# 05_-_CPU_IO.net
KiCad netlist of a schematic drawn in Altium Designer
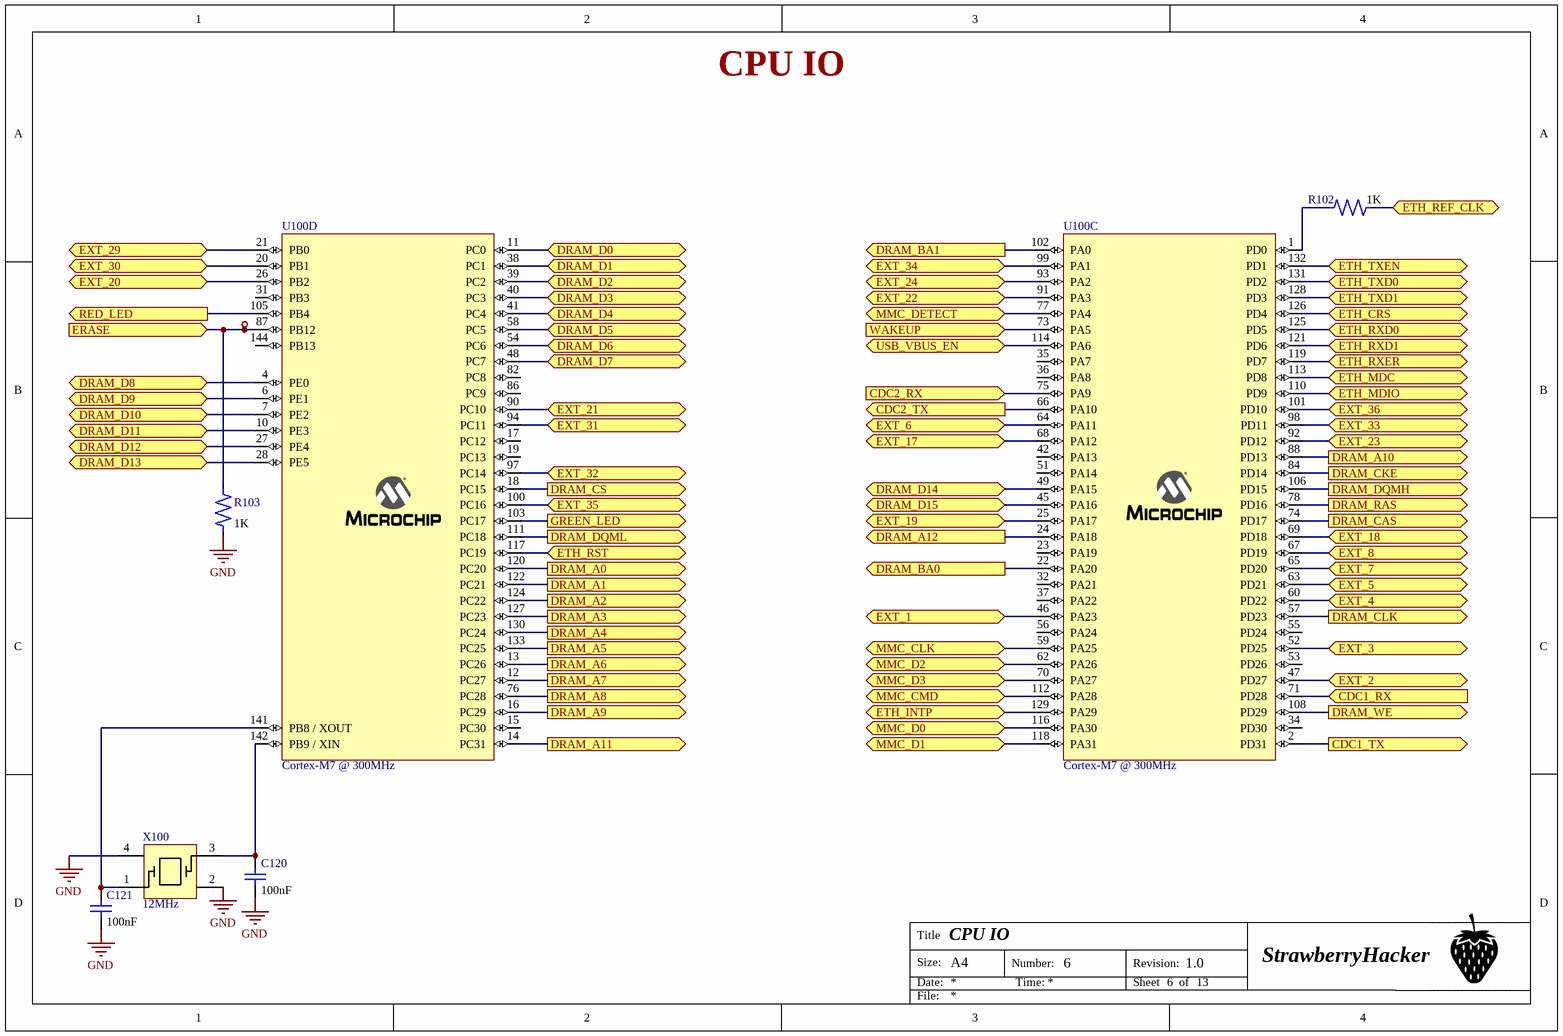
[diagram p0: [05] - CPU IO.SchDoc]

(export (version "E")
  (design (tool "Eeschema 10.0.6"))
  (components
    (comp (ref "C120")
      (value "100nF")
      (footprint "C0402")
      (description "C0402")
      (fields (field (name "Comment") "04023C103KAT2A"))
      (libsource (lib "Passive components") (part "04023C103KAT2A"))
    )
    (comp (ref "C121")
      (value "100nF")
      (footprint "C0402")
      (description "C0402")
      (fields (field (name "Comment") "04023C103KAT2A"))
      (libsource (lib "Passive components") (part "04023C103KAT2A"))
    )
    (comp (ref "R102")
      (value "1K")
      (footprint "R0402")
      (description "R0402")
      (fields (field (name "Comment") "CRCW04020000Z0ED"))
      (libsource (lib "Passive components") (part "CRCW04020000Z0ED"))
    )
    (comp (ref "R103")
      (value "1K")
      (footprint "R0402")
      (description "R0402")
      (fields (field (name "Comment") "CRCW04020000Z0ED"))
      (libsource (lib "Passive components") (part "CRCW04020000Z0ED"))
    )
    (comp (ref "TP100")
      (value "Test point")
      (footprint "TEST POINT")
      (libsource (lib "Miscellaneous") (part "Test point"))
    )
    (comp (ref "U100")
      (value "Cortex-M7 @ 300MHz")
      (footprint "ATSAMS70Q21A-AN")
      (description "ATSAMS70Q21")
      (libsource (lib "Microcontrollers") (part "ATSAMS70Q21A-AN"))
    )
    (comp (ref "X100")
      (value "12MHz")
      (footprint "MCSJK-7U-12.00-12-30-80-B-30")
      (description "Crystal 12MHz 3.2mm x 2.5mm")
      (libsource (lib "Crystals") (part "MCSJK-7U-12.00-12-30-80-B-30"))
    )
  )
  (nets
    (net (code "1") (name "/CDC1_RX") (class "Default")
      (node (ref "U100") (pin "71") (pinfunction "PD28_71") (pintype "bidirectional"))
    )
    (net (code "2") (name "/CDC1_TX") (class "Default")
      (node (ref "U100") (pin "2") (pinfunction "PD31_2") (pintype "bidirectional"))
    )
    (net (code "3") (name "/CDC2_RX") (class "Default")
      (node (ref "U100") (pin "75") (pinfunction "PA9_75") (pintype "bidirectional"))
    )
    (net (code "4") (name "/CDC2_TX") (class "Default")
      (node (ref "U100") (pin "66") (pinfunction "PA10_66") (pintype "bidirectional"))
    )
    (net (code "5") (name "/DRAM_A0") (class "Default")
      (node (ref "U100") (pin "120") (pinfunction "PC20_120") (pintype "bidirectional"))
    )
    (net (code "6") (name "/DRAM_A1") (class "Default")
      (node (ref "U100") (pin "122") (pinfunction "PC21_122") (pintype "bidirectional"))
    )
    (net (code "7") (name "/DRAM_A2") (class "Default")
      (node (ref "U100") (pin "124") (pinfunction "PC22_124") (pintype "bidirectional"))
    )
    (net (code "8") (name "/DRAM_A3") (class "Default")
      (node (ref "U100") (pin "127") (pinfunction "PC23_127") (pintype "bidirectional"))
    )
    (net (code "9") (name "/DRAM_A4") (class "Default")
      (node (ref "U100") (pin "130") (pinfunction "PC24_130") (pintype "bidirectional"))
    )
    (net (code "10") (name "/DRAM_A5") (class "Default")
      (node (ref "U100") (pin "133") (pinfunction "PC25_133") (pintype "bidirectional"))
    )
    (net (code "11") (name "/DRAM_A6") (class "Default")
      (node (ref "U100") (pin "13") (pinfunction "PC26_13") (pintype "bidirectional"))
    )
    (net (code "12") (name "/DRAM_A7") (class "Default")
      (node (ref "U100") (pin "12") (pinfunction "PC27_12") (pintype "bidirectional"))
    )
    (net (code "13") (name "/DRAM_A8") (class "Default")
      (node (ref "U100") (pin "76") (pinfunction "PC28_76") (pintype "bidirectional"))
    )
    (net (code "14") (name "/DRAM_A9") (class "Default")
      (node (ref "U100") (pin "16") (pinfunction "PC29_16") (pintype "bidirectional"))
    )
    (net (code "15") (name "/DRAM_A10") (class "Default")
      (node (ref "U100") (pin "88") (pinfunction "PD13_88") (pintype "bidirectional"))
    )
    (net (code "16") (name "/DRAM_A11") (class "Default")
      (node (ref "U100") (pin "14") (pinfunction "PC31_14") (pintype "bidirectional"))
    )
    (net (code "17") (name "/DRAM_A12") (class "Default")
      (node (ref "U100") (pin "24") (pinfunction "PA18_24") (pintype "bidirectional"))
    )
    (net (code "18") (name "/DRAM_BA0") (class "Default")
      (node (ref "U100") (pin "22") (pinfunction "PA20_22") (pintype "bidirectional"))
    )
    (net (code "19") (name "/DRAM_BA1") (class "Default")
      (node (ref "U100") (pin "102") (pinfunction "PA0_102") (pintype "bidirectional"))
    )
    (net (code "20") (name "/DRAM_CAS") (class "Default")
      (node (ref "U100") (pin "74") (pinfunction "PD17_74") (pintype "bidirectional"))
    )
    (net (code "21") (name "/DRAM_CKE") (class "Default")
      (node (ref "U100") (pin "84") (pinfunction "PD14_84") (pintype "bidirectional"))
    )
    (net (code "22") (name "/DRAM_CLK") (class "Default")
      (node (ref "U100") (pin "57") (pinfunction "PD23_57") (pintype "bidirectional"))
    )
    (net (code "23") (name "/DRAM_CS") (class "Default")
      (node (ref "U100") (pin "18") (pinfunction "PC15_18") (pintype "bidirectional"))
    )
    (net (code "24") (name "/DRAM_D0") (class "Default")
      (node (ref "U100") (pin "11") (pinfunction "PC0_11") (pintype "bidirectional"))
    )
    (net (code "25") (name "/DRAM_D1") (class "Default")
      (node (ref "U100") (pin "38") (pinfunction "PC1_38") (pintype "bidirectional"))
    )
    (net (code "26") (name "/DRAM_D2") (class "Default")
      (node (ref "U100") (pin "39") (pinfunction "PC2_39") (pintype "bidirectional"))
    )
    (net (code "27") (name "/DRAM_D3") (class "Default")
      (node (ref "U100") (pin "40") (pinfunction "PC3_40") (pintype "bidirectional"))
    )
    (net (code "28") (name "/DRAM_D4") (class "Default")
      (node (ref "U100") (pin "41") (pinfunction "PC4_41") (pintype "bidirectional"))
    )
    (net (code "29") (name "/DRAM_D5") (class "Default")
      (node (ref "U100") (pin "58") (pinfunction "PC5_58") (pintype "bidirectional"))
    )
    (net (code "30") (name "/DRAM_D6") (class "Default")
      (node (ref "U100") (pin "54") (pinfunction "PC6_54") (pintype "bidirectional"))
    )
    (net (code "31") (name "/DRAM_D7") (class "Default")
      (node (ref "U100") (pin "48") (pinfunction "PC7_48") (pintype "bidirectional"))
    )
    (net (code "32") (name "/DRAM_D8") (class "Default")
      (node (ref "U100") (pin "4") (pinfunction "PE0_4") (pintype "bidirectional"))
    )
    (net (code "33") (name "/DRAM_D9") (class "Default")
      (node (ref "U100") (pin "6") (pinfunction "PE1_6") (pintype "bidirectional"))
    )
    (net (code "34") (name "/DRAM_D10") (class "Default")
      (node (ref "U100") (pin "7") (pinfunction "PE2_7") (pintype "bidirectional"))
    )
    (net (code "35") (name "/DRAM_D11") (class "Default")
      (node (ref "U100") (pin "10") (pinfunction "PE3_10") (pintype "bidirectional"))
    )
    (net (code "36") (name "/DRAM_D12") (class "Default")
      (node (ref "U100") (pin "27") (pinfunction "PE4_27") (pintype "bidirectional"))
    )
    (net (code "37") (name "/DRAM_D13") (class "Default")
      (node (ref "U100") (pin "28") (pinfunction "PE5_28") (pintype "bidirectional"))
    )
    (net (code "38") (name "/DRAM_D14") (class "Default")
      (node (ref "U100") (pin "49") (pinfunction "PA15_49") (pintype "bidirectional"))
    )
    (net (code "39") (name "/DRAM_D15") (class "Default")
      (node (ref "U100") (pin "45") (pinfunction "PA16_45") (pintype "bidirectional"))
    )
    (net (code "40") (name "/DRAM_DQMH") (class "Default")
      (node (ref "U100") (pin "106") (pinfunction "PD15_106") (pintype "bidirectional"))
    )
    (net (code "41") (name "/DRAM_DQML") (class "Default")
      (node (ref "U100") (pin "111") (pinfunction "PC18_111") (pintype "bidirectional"))
    )
    (net (code "42") (name "/DRAM_RAS") (class "Default")
      (node (ref "U100") (pin "78") (pinfunction "PD16_78") (pintype "bidirectional"))
    )
    (net (code "43") (name "/DRAM_WE") (class "Default")
      (node (ref "U100") (pin "108") (pinfunction "PD29_108") (pintype "bidirectional"))
    )
    (net (code "44") (name "/ERASE") (class "Default")
      (node (ref "R103") (pin "2") (pinfunction "3_2") (pintype "passive"))
      (node (ref "TP100") (pin "1") (pinfunction "33_1") (pintype "passive"))
      (node (ref "U100") (pin "87") (pinfunction "PB12_87") (pintype "bidirectional"))
    )
    (net (code "45") (name "/ETH_CRS") (class "Default")
      (node (ref "U100") (pin "126") (pinfunction "PD4_126") (pintype "bidirectional"))
    )
    (net (code "46") (name "/ETH_INTP") (class "Default")
      (node (ref "U100") (pin "129") (pinfunction "PA29_129") (pintype "bidirectional"))
    )
    (net (code "47") (name "/ETH_MDC") (class "Default")
      (node (ref "U100") (pin "113") (pinfunction "PD8_113") (pintype "bidirectional"))
    )
    (net (code "48") (name "/ETH_MDIO") (class "Default")
      (node (ref "U100") (pin "110") (pinfunction "PD9_110") (pintype "bidirectional"))
    )
    (net (code "49") (name "/ETH_REF_CLK") (class "Default")
      (node (ref "R102") (pin "2") (pinfunction "3_2") (pintype "passive"))
    )
    (net (code "50") (name "/ETH_RST") (class "Default")
      (node (ref "U100") (pin "117") (pinfunction "PC19_117") (pintype "bidirectional"))
    )
    (net (code "51") (name "/ETH_RXD0") (class "Default")
      (node (ref "U100") (pin "125") (pinfunction "PD5_125") (pintype "bidirectional"))
    )
    (net (code "52") (name "/ETH_RXD1") (class "Default")
      (node (ref "U100") (pin "121") (pinfunction "PD6_121") (pintype "bidirectional"))
    )
    (net (code "53") (name "/ETH_RXER") (class "Default")
      (node (ref "U100") (pin "119") (pinfunction "PD7_119") (pintype "bidirectional"))
    )
    (net (code "54") (name "/ETH_TXD0") (class "Default")
      (node (ref "U100") (pin "131") (pinfunction "PD2_131") (pintype "bidirectional"))
    )
    (net (code "55") (name "/ETH_TXD1") (class "Default")
      (node (ref "U100") (pin "128") (pinfunction "PD3_128") (pintype "bidirectional"))
    )
    (net (code "56") (name "/ETH_TXEN") (class "Default")
      (node (ref "U100") (pin "132") (pinfunction "PD1_132") (pintype "bidirectional"))
    )
    (net (code "57") (name "/EXT_1") (class "Default")
      (node (ref "U100") (pin "46") (pinfunction "PA23_46") (pintype "bidirectional"))
    )
    (net (code "58") (name "/EXT_2") (class "Default")
      (node (ref "U100") (pin "47") (pinfunction "PD27_47") (pintype "bidirectional"))
    )
    (net (code "59") (name "/EXT_3") (class "Default")
      (node (ref "U100") (pin "52") (pinfunction "PD25_52") (pintype "bidirectional"))
    )
    (net (code "60") (name "/EXT_4") (class "Default")
      (node (ref "U100") (pin "60") (pinfunction "PD22_60") (pintype "bidirectional"))
    )
    (net (code "61") (name "/EXT_5") (class "Default")
      (node (ref "U100") (pin "63") (pinfunction "PD21_63") (pintype "bidirectional"))
    )
    (net (code "62") (name "/EXT_6") (class "Default")
      (node (ref "U100") (pin "64") (pinfunction "PA11_64") (pintype "bidirectional"))
    )
    (net (code "63") (name "/EXT_7") (class "Default")
      (node (ref "U100") (pin "65") (pinfunction "PD20_65") (pintype "bidirectional"))
    )
    (net (code "64") (name "/EXT_8") (class "Default")
      (node (ref "U100") (pin "67") (pinfunction "PD19_67") (pintype "bidirectional"))
    )
    (net (code "65") (name "/EXT_17") (class "Default")
      (node (ref "U100") (pin "68") (pinfunction "PA12_68") (pintype "bidirectional"))
    )
    (net (code "66") (name "/EXT_18") (class "Default")
      (node (ref "U100") (pin "69") (pinfunction "PD18_69") (pintype "bidirectional"))
    )
    (net (code "67") (name "/EXT_19") (class "Default")
      (node (ref "U100") (pin "25") (pinfunction "PA17_25") (pintype "bidirectional"))
    )
    (net (code "68") (name "/EXT_20") (class "Default")
      (node (ref "U100") (pin "26") (pinfunction "PB2_26") (pintype "bidirectional"))
    )
    (net (code "69") (name "/EXT_21") (class "Default")
      (node (ref "U100") (pin "90") (pinfunction "PC10_90") (pintype "bidirectional"))
    )
    (net (code "70") (name "/EXT_22") (class "Default")
      (node (ref "U100") (pin "91") (pinfunction "PA3_91") (pintype "bidirectional"))
    )
    (net (code "71") (name "/EXT_23") (class "Default")
      (node (ref "U100") (pin "92") (pinfunction "PD12_92") (pintype "bidirectional"))
    )
    (net (code "72") (name "/EXT_24") (class "Default")
      (node (ref "U100") (pin "93") (pinfunction "PA2_93") (pintype "bidirectional"))
    )
    (net (code "73") (name "/EXT_29") (class "Default")
      (node (ref "U100") (pin "21") (pinfunction "PB0_21") (pintype "bidirectional"))
    )
    (net (code "74") (name "/EXT_30") (class "Default")
      (node (ref "U100") (pin "20") (pinfunction "PB1_20") (pintype "bidirectional"))
    )
    (net (code "75") (name "/EXT_31") (class "Default")
      (node (ref "U100") (pin "94") (pinfunction "PC11_94") (pintype "bidirectional"))
    )
    (net (code "76") (name "/EXT_32") (class "Default")
      (node (ref "U100") (pin "97") (pinfunction "PC14_97") (pintype "bidirectional"))
    )
    (net (code "77") (name "/EXT_33") (class "Default")
      (node (ref "U100") (pin "98") (pinfunction "PD11_98") (pintype "bidirectional"))
    )
    (net (code "78") (name "/EXT_34") (class "Default")
      (node (ref "U100") (pin "99") (pinfunction "PA1_99") (pintype "bidirectional"))
    )
    (net (code "79") (name "/EXT_35") (class "Default")
      (node (ref "U100") (pin "100") (pinfunction "PC16_100") (pintype "bidirectional"))
    )
    (net (code "80") (name "/EXT_36") (class "Default")
      (node (ref "U100") (pin "101") (pinfunction "PD10_101") (pintype "bidirectional"))
    )
    (net (code "81") (name "/GREEN_LED") (class "Default")
      (node (ref "U100") (pin "103") (pinfunction "PC17_103") (pintype "bidirectional"))
    )
    (net (code "82") (name "/MMC_CLK") (class "Default")
      (node (ref "U100") (pin "59") (pinfunction "PA25_59") (pintype "bidirectional"))
    )
    (net (code "83") (name "/MMC_CMD") (class "Default")
      (node (ref "U100") (pin "112") (pinfunction "PA28_112") (pintype "bidirectional"))
    )
    (net (code "84") (name "/MMC_D0") (class "Default")
      (node (ref "U100") (pin "116") (pinfunction "PA30_116") (pintype "bidirectional"))
    )
    (net (code "85") (name "/MMC_D1") (class "Default")
      (node (ref "U100") (pin "118") (pinfunction "PA31_118") (pintype "bidirectional"))
    )
    (net (code "86") (name "/MMC_D2") (class "Default")
      (node (ref "U100") (pin "62") (pinfunction "PA26_62") (pintype "bidirectional"))
    )
    (net (code "87") (name "/MMC_D3") (class "Default")
      (node (ref "U100") (pin "70") (pinfunction "PA27_70") (pintype "bidirectional"))
    )
    (net (code "88") (name "/MMC_DETECT") (class "Default")
      (node (ref "U100") (pin "77") (pinfunction "PA4_77") (pintype "bidirectional"))
    )
    (net (code "89") (name "/RED_LED") (class "Default")
      (node (ref "U100") (pin "105") (pinfunction "PB4_105") (pintype "bidirectional"))
    )
    (net (code "90") (name "/USB_VBUS_EN") (class "Default")
      (node (ref "U100") (pin "114") (pinfunction "PA6_114") (pintype "bidirectional"))
    )
    (net (code "91") (name "/WAKEUP") (class "Default")
      (node (ref "U100") (pin "73") (pinfunction "PA5_73") (pintype "bidirectional"))
    )
    (net (code "92") (name "GND") (class "Default")
      (node (ref "C120") (pin "1") (pinfunction "1_1") (pintype "passive"))
      (node (ref "C121") (pin "1") (pinfunction "1_1") (pintype "passive"))
      (node (ref "R103") (pin "1") (pinfunction "1_1") (pintype "passive"))
      (node (ref "X100") (pin "2") (pinfunction "2_2") (pintype "passive"))
      (node (ref "X100") (pin "4") (pinfunction "4_4") (pintype "passive"))
    )
    (net (code "93") (name "Net-(U100C-PD0)") (class "Default")
      (node (ref "R102") (pin "1") (pinfunction "1_1") (pintype "passive"))
      (node (ref "U100") (pin "1") (pinfunction "PD0_1") (pintype "bidirectional"))
    )
    (net (code "94") (name "Net-(U100D-PB8_{slash}_XOUT)") (class "Default")
      (node (ref "C121") (pin "2") (pinfunction "2_2") (pintype "passive"))
      (node (ref "U100") (pin "141") (pinfunction "PB8_/_XOUT_141") (pintype "bidirectional"))
      (node (ref "X100") (pin "1") (pinfunction "2_1") (pintype "passive"))
    )
    (net (code "95") (name "Net-(U100D-PB9_{slash}_XIN)") (class "Default")
      (node (ref "C120") (pin "2") (pinfunction "2_2") (pintype "passive"))
      (node (ref "U100") (pin "142") (pinfunction "PB9_/_XIN_142") (pintype "bidirectional"))
      (node (ref "X100") (pin "3") (pinfunction "2_3") (pintype "passive"))
    )
    (net (code "96") (name "unconnected-(U100C-PA7-Pad35)") (class "Default")
      (node (ref "U100") (pin "35") (pinfunction "PA7_35") (pintype "bidirectional"))
    )
    (net (code "97") (name "unconnected-(U100C-PA8-Pad36)") (class "Default")
      (node (ref "U100") (pin "36") (pinfunction "PA8_36") (pintype "bidirectional"))
    )
    (net (code "98") (name "unconnected-(U100C-PA13-Pad42)") (class "Default")
      (node (ref "U100") (pin "42") (pinfunction "PA13_42") (pintype "bidirectional"))
    )
    (net (code "99") (name "unconnected-(U100C-PA14-Pad51)") (class "Default")
      (node (ref "U100") (pin "51") (pinfunction "PA14_51") (pintype "bidirectional"))
    )
    (net (code "100") (name "unconnected-(U100C-PA19-Pad23)") (class "Default")
      (node (ref "U100") (pin "23") (pinfunction "PA19_23") (pintype "bidirectional"))
    )
    (net (code "101") (name "unconnected-(U100C-PA21-Pad32)") (class "Default")
      (node (ref "U100") (pin "32") (pinfunction "PA21_32") (pintype "bidirectional"))
    )
    (net (code "102") (name "unconnected-(U100C-PA22-Pad37)") (class "Default")
      (node (ref "U100") (pin "37") (pinfunction "PA22_37") (pintype "bidirectional"))
    )
    (net (code "103") (name "unconnected-(U100C-PA24-Pad56)") (class "Default")
      (node (ref "U100") (pin "56") (pinfunction "PA24_56") (pintype "bidirectional"))
    )
    (net (code "104") (name "unconnected-(U100C-PD24-Pad55)") (class "Default")
      (node (ref "U100") (pin "55") (pinfunction "PD24_55") (pintype "bidirectional"))
    )
    (net (code "105") (name "unconnected-(U100C-PD26-Pad53)") (class "Default")
      (node (ref "U100") (pin "53") (pinfunction "PD26_53") (pintype "bidirectional"))
    )
    (net (code "106") (name "unconnected-(U100C-PD30-Pad34)") (class "Default")
      (node (ref "U100") (pin "34") (pinfunction "PD30_34") (pintype "bidirectional"))
    )
    (net (code "107") (name "unconnected-(U100D-PB3-Pad31)") (class "Default")
      (node (ref "U100") (pin "31") (pinfunction "PB3_31") (pintype "bidirectional"))
    )
    (net (code "108") (name "unconnected-(U100D-PB13-Pad144)") (class "Default")
      (node (ref "U100") (pin "144") (pinfunction "PB13_144") (pintype "bidirectional"))
    )
    (net (code "109") (name "unconnected-(U100D-PC8-Pad82)") (class "Default")
      (node (ref "U100") (pin "82") (pinfunction "PC8_82") (pintype "bidirectional"))
    )
    (net (code "110") (name "unconnected-(U100D-PC9-Pad86)") (class "Default")
      (node (ref "U100") (pin "86") (pinfunction "PC9_86") (pintype "bidirectional"))
    )
    (net (code "111") (name "unconnected-(U100D-PC12-Pad17)") (class "Default")
      (node (ref "U100") (pin "17") (pinfunction "PC12_17") (pintype "bidirectional"))
    )
    (net (code "112") (name "unconnected-(U100D-PC13-Pad19)") (class "Default")
      (node (ref "U100") (pin "19") (pinfunction "PC13_19") (pintype "bidirectional"))
    )
    (net (code "113") (name "unconnected-(U100D-PC30-Pad15)") (class "Default")
      (node (ref "U100") (pin "15") (pinfunction "PC30_15") (pintype "bidirectional"))
    )
  )
)
